# imu.net
KiCad netlist of a schematic drawn in Altium Designer
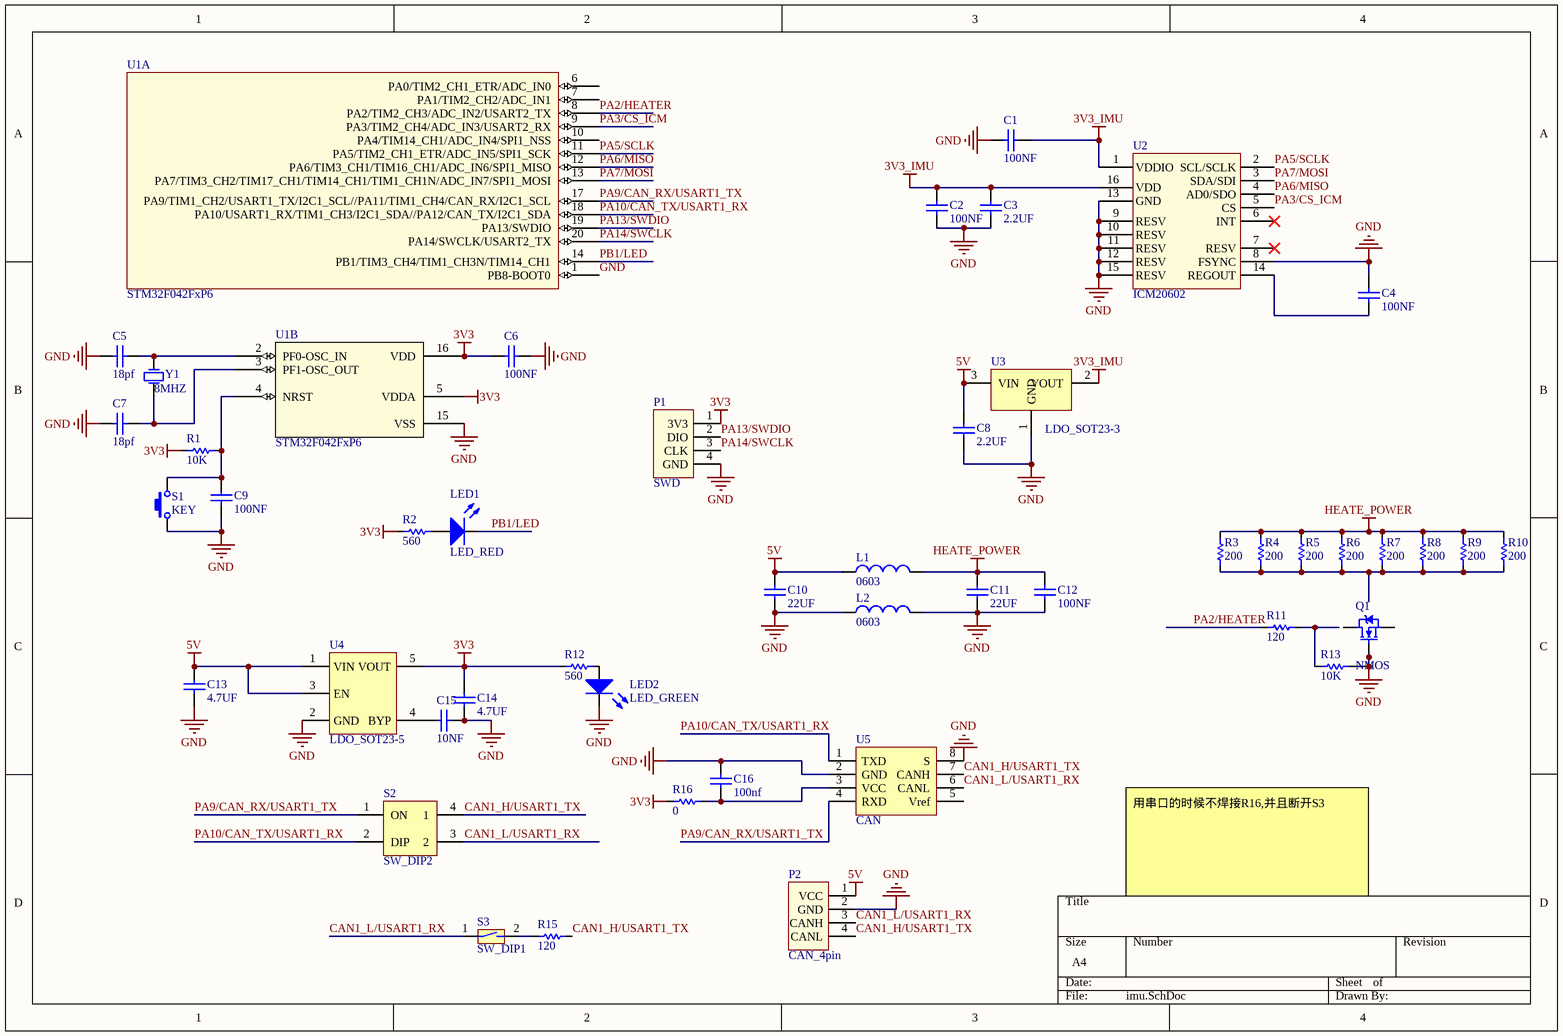
[diagram p0: imu.SchDoc]

(export (version "E")
  (design (tool "Eeschema 10.0.6"))
  (components
    (comp (ref "C1")
      (value "100NF")
      (footprint "MyComponents_v2.5:0402")
      (description "Capacitor")
      (fields (field (name "PUBLISHER") "Altium Limited"))
      (libsource (lib "MyComponents_v2.5") (part "Cap"))
    )
    (comp (ref "C2")
      (value "100NF")
      (footprint "MyComponents_v2.5:0402")
      (description "Capacitor")
      (fields (field (name "PUBLISHER") "Altium Limited"))
      (libsource (lib "MyComponents_v2.5") (part "Cap"))
    )
    (comp (ref "C3")
      (value "2.2UF")
      (footprint "MyComponents_v2.5:0402")
      (description "Capacitor")
      (fields (field (name "PUBLISHER") "Altium Limited"))
      (libsource (lib "MyComponents_v2.5") (part "Cap"))
    )
    (comp (ref "C4")
      (value "100NF")
      (footprint "MyComponents_v2.5:0402")
      (description "Capacitor")
      (fields (field (name "PUBLISHER") "Altium Limited"))
      (libsource (lib "MyComponents_v2.5") (part "Cap"))
    )
    (comp (ref "C5")
      (value "18pf")
      (footprint "MyComponents_v2.5:0402C")
      (description "Capacitor")
      (fields (field (name "PUBLISHER") "Altium Limited"))
      (libsource (lib "MyComponents_v2.5") (part "Cap"))
    )
    (comp (ref "C6")
      (value "100NF")
      (footprint "MyComponents_v2.5:0603C")
      (description "Capacitor")
      (fields (field (name "PUBLISHER") "Altium Limited"))
      (libsource (lib "MyComponents_v2.5") (part "Cap"))
    )
    (comp (ref "C7")
      (value "18pf")
      (footprint "MyComponents_v2.5:0402C")
      (description "Capacitor")
      (fields (field (name "PUBLISHER") "Altium Limited"))
      (libsource (lib "MyComponents_v2.5") (part "Cap"))
    )
    (comp (ref "C8")
      (value "2.2UF")
      (footprint "MyComponents_v2.5:0603C")
      (description "Capacitor")
      (fields (field (name "PUBLISHER") "Altium Limited"))
      (libsource (lib "MyComponents_v2.5") (part "Cap"))
    )
    (comp (ref "C9")
      (value "100NF")
      (footprint "MyComponents_v2.5:0603C")
      (description "Capacitor")
      (fields (field (name "PUBLISHER") "Altium Limited"))
      (libsource (lib "MyComponents_v2.5") (part "Cap"))
    )
    (comp (ref "C10")
      (value "22UF")
      (footprint "MyComponents_v2.5:0805c")
      (description "Capacitor")
      (fields (field (name "PUBLISHER") "Altium Limited"))
      (libsource (lib "MyComponents_v2.5") (part "Cap"))
    )
    (comp (ref "C11")
      (value "22UF")
      (footprint "MyComponents_v2.5:0805c")
      (description "Capacitor")
      (fields (field (name "PUBLISHER") "Altium Limited"))
      (libsource (lib "MyComponents_v2.5") (part "Cap"))
    )
    (comp (ref "C12")
      (value "100NF")
      (footprint "MyComponents_v2.5:0603C")
      (description "Capacitor")
      (fields (field (name "PUBLISHER") "Altium Limited"))
      (libsource (lib "MyComponents_v2.5") (part "Cap"))
    )
    (comp (ref "C13")
      (value "4.7UF")
      (footprint "MyComponents_v2.5:0603C")
      (description "Capacitor")
      (fields (field (name "PUBLISHER") "Altium Limited"))
      (libsource (lib "MyComponents_v2.5") (part "Cap"))
    )
    (comp (ref "C14")
      (value "4.7UF")
      (footprint "MyComponents_v2.5:0603C")
      (description "Capacitor")
      (fields (field (name "PUBLISHER") "Altium Limited"))
      (libsource (lib "MyComponents_v2.5") (part "Cap"))
    )
    (comp (ref "C15")
      (value "10NF")
      (footprint "MyComponents_v2.5:0603C")
      (description "Capacitor")
      (fields (field (name "PUBLISHER") "Altium Limited"))
      (libsource (lib "MyComponents_v2.5") (part "Cap"))
    )
    (comp (ref "C16")
      (value "100nf")
      (footprint "MyComponents_v2.5:0603C")
      (description "Capacitor")
      (fields (field (name "PUBLISHER") "Altium Limited"))
      (libsource (lib "MyComponents_v2.5") (part "Cap"))
    )
    (comp (ref "L1")
      (value "0603")
      (footprint "MyComponents_v2.5:0603")
      (description "Inductor")
      (fields (field (name "PUBLISHER") "Altium Limited"))
      (libsource (lib "MyComponents_v2.5") (part "Inductor"))
    )
    (comp (ref "L2")
      (value "0603")
      (footprint "MyComponents_v2.5:0603")
      (description "Inductor")
      (fields (field (name "PUBLISHER") "Altium Limited"))
      (libsource (lib "MyComponents_v2.5") (part "Inductor"))
    )
    (comp (ref "LED1")
      (value "LED_RED")
      (footprint "MyComponents_v2.5:0603LED_R")
      (description "Typical RED, GREEN, YELLOW, AMBER GaAs LED")
      (fields (field (name "PUBLISHER") "Altium Limited"))
      (libsource (lib "MyComponents_v2.5") (part "LED"))
    )
    (comp (ref "LED2")
      (value "LED_GREEN")
      (footprint "MyComponents_v2.5:0603LED_R")
      (description "Typical RED, GREEN, YELLOW, AMBER GaAs LED")
      (fields (field (name "PUBLISHER") "Altium Limited"))
      (libsource (lib "MyComponents_v2.5") (part "LED"))
    )
    (comp (ref "P1")
      (value "SWD")
      (footprint "MyComponents_v2.5:A1.25WF-4P")
      (libsource (lib "MyComponents_v2.5") (part "SWD_HEADER"))
    )
    (comp (ref "P2")
      (value "CAN_4pin")
      (footprint "MyComponents_v2.5:HY2.00MM 4X1 SMT")
      (description "CAN 4pin，带5V电源，HY2.0-4A")
      (libsource (lib "MyComponents_v2.5") (part "CAN_4pin"))
    )
    (comp (ref "Q1")
      (value "NMOS")
      (footprint "MyComponents_v2.5:SOT-23-3")
      (description "N-Channel Power MOSFET")
      (fields (field (name "PUBLISHER") "Altium Limited"))
      (libsource (lib "MyComponents_v2.5") (part "NMOS(SOT23)"))
    )
    (comp (ref "R1")
      (value "10K")
      (footprint "MyComponents_v2.5:0603R")
      (description "Resistor")
      (fields (field (name "PUBLISHER") "Altium Limited"))
      (libsource (lib "MyComponents_v2.5") (part "Res1"))
    )
    (comp (ref "R2")
      (value "560")
      (footprint "MyComponents_v2.5:0603R")
      (description "Resistor")
      (fields (field (name "PUBLISHER") "Altium Limited"))
      (libsource (lib "MyComponents_v2.5") (part "Res1"))
    )
    (comp (ref "R3")
      (value "200")
      (footprint "MyComponents_v2.5:0603R")
      (description "Resistor")
      (fields (field (name "PUBLISHER") "Altium Limited"))
      (libsource (lib "MyComponents_v2.5") (part "Res1"))
    )
    (comp (ref "R4")
      (value "200")
      (footprint "MyComponents_v2.5:0603R")
      (description "Resistor")
      (fields (field (name "PUBLISHER") "Altium Limited"))
      (libsource (lib "MyComponents_v2.5") (part "Res1"))
    )
    (comp (ref "R5")
      (value "200")
      (footprint "MyComponents_v2.5:0603R")
      (description "Resistor")
      (fields (field (name "PUBLISHER") "Altium Limited"))
      (libsource (lib "MyComponents_v2.5") (part "Res1"))
    )
    (comp (ref "R6")
      (value "200")
      (footprint "MyComponents_v2.5:0603R")
      (description "Resistor")
      (fields (field (name "PUBLISHER") "Altium Limited"))
      (libsource (lib "MyComponents_v2.5") (part "Res1"))
    )
    (comp (ref "R7")
      (value "200")
      (footprint "MyComponents_v2.5:0603R")
      (description "Resistor")
      (fields (field (name "PUBLISHER") "Altium Limited"))
      (libsource (lib "MyComponents_v2.5") (part "Res1"))
    )
    (comp (ref "R8")
      (value "200")
      (footprint "MyComponents_v2.5:0603R")
      (description "Resistor")
      (fields (field (name "PUBLISHER") "Altium Limited"))
      (libsource (lib "MyComponents_v2.5") (part "Res1"))
    )
    (comp (ref "R9")
      (value "200")
      (footprint "MyComponents_v2.5:0603R")
      (description "Resistor")
      (fields (field (name "PUBLISHER") "Altium Limited"))
      (libsource (lib "MyComponents_v2.5") (part "Res1"))
    )
    (comp (ref "R10")
      (value "200")
      (footprint "MyComponents_v2.5:0603R")
      (description "Resistor")
      (fields (field (name "PUBLISHER") "Altium Limited"))
      (libsource (lib "MyComponents_v2.5") (part "Res1"))
    )
    (comp (ref "R11")
      (value "120")
      (footprint "MyComponents_v2.5:0603R")
      (description "Resistor")
      (fields (field (name "PUBLISHER") "Altium Limited"))
      (libsource (lib "MyComponents_v2.5") (part "Res1"))
    )
    (comp (ref "R12")
      (value "560")
      (footprint "MyComponents_v2.5:0603R")
      (description "Resistor")
      (fields (field (name "PUBLISHER") "Altium Limited"))
      (libsource (lib "MyComponents_v2.5") (part "Res1"))
    )
    (comp (ref "R13")
      (value "10K")
      (footprint "MyComponents_v2.5:0603R")
      (description "Resistor")
      (fields (field (name "PUBLISHER") "Altium Limited"))
      (libsource (lib "MyComponents_v2.5") (part "Res1"))
    )
    (comp (ref "R15")
      (value "120")
      (footprint "MyComponents_v2.5:0603R")
      (description "Resistor")
      (fields (field (name "PUBLISHER") "Altium Limited"))
      (libsource (lib "MyComponents_v2.5") (part "Res1"))
    )
    (comp (ref "R16")
      (value "0")
      (footprint "MyComponents_v2.5:0603R")
      (description "Resistor")
      (fields (field (name "PUBLISHER") "Altium Limited"))
      (libsource (lib "MyComponents_v2.5") (part "Res1"))
    )
    (comp (ref "S1")
      (value "KEY")
      (footprint "MyComponents_v2.5:SW 3mmx4mm")
      (description "Button")
      (fields (field (name "PUBLISHER") "Altium Limited"))
      (libsource (lib "MyComponents_v2.5") (part "PushButton_2p"))
    )
    (comp (ref "S2")
      (value "SW_DIP2")
      (footprint "MyComponents_v2.5:SW_DIP_2x2")
      (libsource (lib "MyComponents_v2.5") (part "SW_DIP 2"))
    )
    (comp (ref "S3")
      (value "SW_DIP1")
      (footprint "MyComponents_v2.5:MSK-12C01-07")
      (libsource (lib "MyComponents_v2.5") (part "SW_DIP 1"))
    )
    (comp (ref "U1")
      (value "STM32F042FxP6")
      (footprint "MyComponents_v2.5:TSSOP20")
      (description "Imported")
      (fields (field (name "MANUFACTURER_PART_NUMBER") "stm32f042gxu"))
      (libsource (lib "MyComponents_v2.5") (part "STM32F042FxP6"))
    )
    (comp (ref "U2")
      (value "ICM20602")
      (footprint "MyComponents_v2.5:LGA-16")
      (libsource (lib "MyComponents_v2.5") (part "ICM20602"))
    )
    (comp (ref "U3")
      (value "LDO_SOT23-3")
      (footprint "MyComponents_v2.5:SOT-23-3")
      (libsource (lib "MyComponents_v2.5") (part "LDO_SOT23-3"))
    )
    (comp (ref "U4")
      (value "LDO_SOT23-5")
      (footprint "MyComponents_v2.5:SOT-23-5 L")
      (libsource (lib "MyComponents_v2.5") (part "LDO_SOT23-5"))
    )
    (comp (ref "U5")
      (value "CAN")
      (footprint "MyComponents_v2.5:SOT-23-8")
      (libsource (lib "MyComponents_v2.5") (part "CAN"))
    )
    (comp (ref "Y1")
      (value "8MHZ")
      (footprint "MyComponents_v2.5:NX3225GD")
      (description "Crystal Oscillator")
      (fields (field (name "PUBLISHER") "Altium Limited"))
      (libsource (lib "MyComponents_v2.5") (part "XTAL"))
    )
  )
  (nets
    (net (code "1") (name "/CAN1_H{slash}USART1_TX") (class "Default")
      (node (ref "P2") (pin "4") (pinfunction "CANL_4") (pintype "passive"))
      (node (ref "R15") (pin "2") (pinfunction "2_2") (pintype "passive"))
      (node (ref "S2") (pin "4") (pinfunction "1_4") (pintype "passive"))
      (node (ref "U5") (pin "7") (pinfunction "CANH_7") (pintype "passive"))
    )
    (net (code "2") (name "/CAN1_L{slash}USART1_RX") (class "Default")
      (node (ref "P2") (pin "3") (pinfunction "CANH_3") (pintype "passive"))
      (node (ref "S2") (pin "3") (pinfunction "2_3") (pintype "passive"))
      (node (ref "S3") (pin "1") (pinfunction "ON_1") (pintype "passive"))
      (node (ref "U5") (pin "6") (pinfunction "CANL_6") (pintype "passive"))
    )
    (net (code "3") (name "/PA2{slash}HEATER") (class "Default")
      (node (ref "R11") (pin "2") (pinfunction "2_2") (pintype "passive"))
      (node (ref "U1") (pin "8") (pinfunction "PA2/TIM2_CH3/ADC_IN2/USART2_TX_8") (pintype "bidirectional"))
    )
    (net (code "4") (name "/PA3{slash}CS_ICM") (class "Default")
      (node (ref "U1") (pin "9") (pinfunction "PA3/TIM2_CH4/ADC_IN3/USART2_RX_9") (pintype "bidirectional"))
      (node (ref "U2") (pin "5") (pinfunction "CS_5") (pintype "passive"))
    )
    (net (code "5") (name "/PA5{slash}SCLK") (class "Default")
      (node (ref "U1") (pin "11") (pinfunction "PA5/TIM2_CH1_ETR/ADC_IN5/SPI1_SCK_11") (pintype "bidirectional"))
      (node (ref "U2") (pin "2") (pinfunction "SCL/SCLK_2") (pintype "passive"))
    )
    (net (code "6") (name "/PA6{slash}MISO") (class "Default")
      (node (ref "U1") (pin "12") (pinfunction "PA6/TIM3_CH1/TIM16_CH1/ADC_IN6/SPI1_MISO_12") (pintype "bidirectional"))
      (node (ref "U2") (pin "4") (pinfunction "AD0/SDO_4") (pintype "passive"))
    )
    (net (code "7") (name "/PA7{slash}MOSI") (class "Default")
      (node (ref "U1") (pin "13") (pinfunction "PA7/TIM3_CH2/TIM17_CH1/TIM14_CH1/TIM1_CH1N/ADC_IN7/SPI1_MOSI_13") (pintype "bidirectional"))
      (node (ref "U2") (pin "3") (pinfunction "SDA/SDI_3") (pintype "passive"))
    )
    (net (code "8") (name "/PA9{slash}CAN_RX{slash}USART1_TX") (class "Default")
      (node (ref "S2") (pin "1") (pinfunction "ON_1") (pintype "passive"))
      (node (ref "U1") (pin "17") (pinfunction "PA9/TIM1_CH2/USART1_TX/I2C1_SCL//PA11/TIM1_CH4/CAN_RX/I2C1_SCL_17") (pintype "bidirectional"))
      (node (ref "U5") (pin "4") (pinfunction "RXD_4") (pintype "passive"))
    )
    (net (code "9") (name "/PA10{slash}CAN_TX{slash}USART1_RX") (class "Default")
      (node (ref "S2") (pin "2") (pinfunction "DIP_2") (pintype "passive"))
      (node (ref "U1") (pin "18") (pinfunction "PA10/USART1_RX/TIM1_CH3/I2C1_SDA//PA12/CAN_TX/I2C1_SDA_18") (pintype "bidirectional"))
      (node (ref "U5") (pin "1") (pinfunction "TXD_1") (pintype "passive"))
    )
    (net (code "10") (name "/PA13{slash}SWDIO") (class "Default")
      (node (ref "P1") (pin "2") (pinfunction "DIO_2") (pintype "passive"))
      (node (ref "U1") (pin "19") (pinfunction "PA13/SWDIO_19") (pintype "bidirectional"))
    )
    (net (code "11") (name "/PA14{slash}SWCLK") (class "Default")
      (node (ref "P1") (pin "3") (pinfunction "CLK_3") (pintype "passive"))
      (node (ref "U1") (pin "20") (pinfunction "PA14/SWCLK/USART2_TX_20") (pintype "bidirectional"))
    )
    (net (code "12") (name "/PB1{slash}LED") (class "Default")
      (node (ref "LED1") (pin "2") (pinfunction "2_2") (pintype "passive"))
      (node (ref "U1") (pin "14") (pinfunction "PB1/TIM3_CH4/TIM1_CH3N/TIM14_CH1_14") (pintype "bidirectional"))
    )
    (net (code "13") (name "3V3") (class "Default")
      (node (ref "C14") (pin "1") (pinfunction "1_1") (pintype "passive"))
      (node (ref "C6") (pin "2") (pinfunction "2_2") (pintype "passive"))
      (node (ref "P1") (pin "1") (pinfunction "3V3_1") (pintype "passive"))
      (node (ref "R1") (pin "1") (pinfunction "1_1") (pintype "passive"))
      (node (ref "R12") (pin "1") (pinfunction "1_1") (pintype "passive"))
      (node (ref "R16") (pin "1") (pinfunction "1_1") (pintype "passive"))
      (node (ref "R2") (pin "1") (pinfunction "1_1") (pintype "passive"))
      (node (ref "U1") (pin "16") (pinfunction "VDD_16") (pintype "power_in"))
      (node (ref "U1") (pin "5") (pinfunction "VDDA_5") (pintype "power_in"))
      (node (ref "U4") (pin "5") (pinfunction "VOUT_5") (pintype "passive"))
    )
    (net (code "14") (name "3V3_IMU") (class "Default")
      (node (ref "C1") (pin "1") (pinfunction "1_1") (pintype "passive"))
      (node (ref "C2") (pin "2") (pinfunction "2_2") (pintype "passive"))
      (node (ref "C3") (pin "1") (pinfunction "1_1") (pintype "passive"))
      (node (ref "U2") (pin "1") (pinfunction "VDDIO_1") (pintype "passive"))
      (node (ref "U2") (pin "16") (pinfunction "VDD_16") (pintype "passive"))
      (node (ref "U3") (pin "2") (pinfunction "VOUT_2") (pintype "passive"))
    )
    (net (code "15") (name "5V") (class "Default")
      (node (ref "C10") (pin "1") (pinfunction "1_1") (pintype "passive"))
      (node (ref "C13") (pin "2") (pinfunction "2_2") (pintype "passive"))
      (node (ref "C8") (pin "1") (pinfunction "1_1") (pintype "passive"))
      (node (ref "L1") (pin "1") (pinfunction "1_1") (pintype "passive"))
      (node (ref "P2") (pin "1") (pinfunction "VCC_1") (pintype "passive"))
      (node (ref "U3") (pin "3") (pinfunction "VIN_3") (pintype "passive"))
      (node (ref "U4") (pin "1") (pinfunction "VIN_1") (pintype "passive"))
      (node (ref "U4") (pin "3") (pinfunction "EN_3") (pintype "passive"))
    )
    (net (code "16") (name "GND") (class "Default")
      (node (ref "C1") (pin "2") (pinfunction "2_2") (pintype "passive"))
      (node (ref "C10") (pin "2") (pinfunction "2_2") (pintype "passive"))
      (node (ref "C11") (pin "2") (pinfunction "2_2") (pintype "passive"))
      (node (ref "C12") (pin "2") (pinfunction "2_2") (pintype "passive"))
      (node (ref "C13") (pin "1") (pinfunction "1_1") (pintype "passive"))
      (node (ref "C14") (pin "2") (pinfunction "2_2") (pintype "passive"))
      (node (ref "C15") (pin "1") (pinfunction "1_1") (pintype "passive"))
      (node (ref "C16") (pin "1") (pinfunction "1_1") (pintype "passive"))
      (node (ref "C2") (pin "1") (pinfunction "1_1") (pintype "passive"))
      (node (ref "C3") (pin "2") (pinfunction "2_2") (pintype "passive"))
      (node (ref "C4") (pin "1") (pinfunction "1_1") (pintype "passive"))
      (node (ref "C5") (pin "1") (pinfunction "1_1") (pintype "passive"))
      (node (ref "C6") (pin "1") (pinfunction "1_1") (pintype "passive"))
      (node (ref "C7") (pin "1") (pinfunction "1_1") (pintype "passive"))
      (node (ref "C8") (pin "2") (pinfunction "2_2") (pintype "passive"))
      (node (ref "C9") (pin "1") (pinfunction "1_1") (pintype "passive"))
      (node (ref "L2") (pin "1") (pinfunction "1_1") (pintype "passive"))
      (node (ref "L2") (pin "2") (pinfunction "2_2") (pintype "passive"))
      (node (ref "LED2") (pin "2") (pinfunction "2_2") (pintype "passive"))
      (node (ref "P1") (pin "4") (pinfunction "GND_4") (pintype "passive"))
      (node (ref "P2") (pin "2") (pinfunction "GND_2") (pintype "passive"))
      (node (ref "Q1") (pin "1") (pinfunction "G_1") (pintype "passive"))
      (node (ref "R13") (pin "1") (pinfunction "1_1") (pintype "passive"))
      (node (ref "S1") (pin "1") (pinfunction "1_1") (pintype "passive"))
      (node (ref "U1") (pin "1") (pinfunction "PB8-BOOT0_1") (pintype "bidirectional"))
      (node (ref "U1") (pin "15") (pinfunction "VSS_15") (pintype "power_in"))
      (node (ref "U2") (pin "10") (pinfunction "RESV_10") (pintype "passive"))
      (node (ref "U2") (pin "11") (pinfunction "RESV_11") (pintype "passive"))
      (node (ref "U2") (pin "12") (pinfunction "RESV_12") (pintype "passive"))
      (node (ref "U2") (pin "13") (pinfunction "GND_13") (pintype "passive"))
      (node (ref "U2") (pin "15") (pinfunction "RESV_15") (pintype "passive"))
      (node (ref "U2") (pin "8") (pinfunction "FSYNC_8") (pintype "passive"))
      (node (ref "U2") (pin "9") (pinfunction "RESV_9") (pintype "passive"))
      (node (ref "U3") (pin "1") (pinfunction "GND_1") (pintype "passive"))
      (node (ref "U4") (pin "2") (pinfunction "GND_2") (pintype "passive"))
      (node (ref "U5") (pin "2") (pinfunction "GND_2") (pintype "passive"))
      (node (ref "U5") (pin "8") (pinfunction "S_8") (pintype "passive"))
    )
    (net (code "17") (name "HEATE_POWER") (class "Default")
      (node (ref "C11") (pin "1") (pinfunction "1_1") (pintype "passive"))
      (node (ref "C12") (pin "1") (pinfunction "1_1") (pintype "passive"))
      (node (ref "L1") (pin "2") (pinfunction "2_2") (pintype "passive"))
      (node (ref "R10") (pin "2") (pinfunction "2_2") (pintype "passive"))
      (node (ref "R3") (pin "2") (pinfunction "2_2") (pintype "passive"))
      (node (ref "R4") (pin "2") (pinfunction "2_2") (pintype "passive"))
      (node (ref "R5") (pin "2") (pinfunction "2_2") (pintype "passive"))
      (node (ref "R6") (pin "2") (pinfunction "2_2") (pintype "passive"))
      (node (ref "R7") (pin "2") (pinfunction "2_2") (pintype "passive"))
      (node (ref "R8") (pin "2") (pinfunction "2_2") (pintype "passive"))
      (node (ref "R9") (pin "2") (pinfunction "2_2") (pintype "passive"))
    )
    (net (code "18") (name "Net-(LED1-Pad1)") (class "Default")
      (node (ref "LED1") (pin "1") (pinfunction "1_1") (pintype "passive"))
      (node (ref "R2") (pin "2") (pinfunction "2_2") (pintype "passive"))
    )
    (net (code "19") (name "Net-(LED2-Pad1)") (class "Default")
      (node (ref "LED2") (pin "1") (pinfunction "1_1") (pintype "passive"))
      (node (ref "R12") (pin "2") (pinfunction "2_2") (pintype "passive"))
    )
    (net (code "20") (name "Net-(R10-Pad1)") (class "Default")
      (node (ref "R10") (pin "1") (pinfunction "1_1") (pintype "passive"))
      (node (ref "R3") (pin "1") (pinfunction "1_1") (pintype "passive"))
      (node (ref "R4") (pin "1") (pinfunction "1_1") (pintype "passive"))
      (node (ref "R5") (pin "1") (pinfunction "1_1") (pintype "passive"))
      (node (ref "R6") (pin "1") (pinfunction "1_1") (pintype "passive"))
      (node (ref "R7") (pin "1") (pinfunction "1_1") (pintype "passive"))
      (node (ref "R8") (pin "1") (pinfunction "1_1") (pintype "passive"))
      (node (ref "R9") (pin "1") (pinfunction "1_1") (pintype "passive"))
    )
    (net (code "21") (name "Net-(R11-Pad1)") (class "Default")
      (node (ref "R11") (pin "1") (pinfunction "1_1") (pintype "passive"))
      (node (ref "R13") (pin "2") (pinfunction "2_2") (pintype "passive"))
    )
    (net (code "22") (name "Net-(S3-DIP)") (class "Default")
      (node (ref "R15") (pin "1") (pinfunction "1_1") (pintype "passive"))
      (node (ref "S3") (pin "2") (pinfunction "DIP_2") (pintype "passive"))
    )
    (net (code "23") (name "Net-(U1B-NRST)") (class "Default")
      (node (ref "C9") (pin "2") (pinfunction "2_2") (pintype "passive"))
      (node (ref "R1") (pin "2") (pinfunction "2_2") (pintype "passive"))
      (node (ref "S1") (pin "2") (pinfunction "2_2") (pintype "passive"))
      (node (ref "U1") (pin "4") (pinfunction "NRST_4") (pintype "bidirectional"))
    )
    (net (code "24") (name "Net-(U1B-PF0-OSC_IN)") (class "Default")
      (node (ref "C5") (pin "2") (pinfunction "2_2") (pintype "passive"))
      (node (ref "U1") (pin "2") (pinfunction "PF0-OSC_IN_2") (pintype "bidirectional"))
      (node (ref "Y1") (pin "2") (pinfunction "OSC2_2") (pintype "passive"))
    )
    (net (code "25") (name "Net-(U1B-PF1-OSC_OUT)") (class "Default")
      (node (ref "C7") (pin "2") (pinfunction "2_2") (pintype "passive"))
      (node (ref "U1") (pin "3") (pinfunction "PF1-OSC_OUT_3") (pintype "bidirectional"))
      (node (ref "Y1") (pin "1") (pinfunction "OSC1_1") (pintype "passive"))
    )
    (net (code "26") (name "Net-(U2-REGOUT)") (class "Default")
      (node (ref "C4") (pin "2") (pinfunction "2_2") (pintype "passive"))
      (node (ref "U2") (pin "14") (pinfunction "REGOUT_14") (pintype "passive"))
    )
    (net (code "27") (name "Net-(U4-BYP)") (class "Default")
      (node (ref "C15") (pin "2") (pinfunction "2_2") (pintype "passive"))
      (node (ref "U4") (pin "4") (pinfunction "BYP_4") (pintype "passive"))
    )
    (net (code "28") (name "Net-(U5-VCC)") (class "Default")
      (node (ref "C16") (pin "2") (pinfunction "2_2") (pintype "passive"))
      (node (ref "R16") (pin "2") (pinfunction "2_2") (pintype "passive"))
      (node (ref "U5") (pin "3") (pinfunction "VCC_3") (pintype "passive"))
    )
    (net (code "29") (name "unconnected-(Q1-D-Pad3)") (class "Default")
      (node (ref "Q1") (pin "3") (pinfunction "D_3") (pintype "passive"))
    )
    (net (code "30") (name "unconnected-(Q1-S-Pad2)") (class "Default")
      (node (ref "Q1") (pin "2") (pinfunction "S_2") (pintype "passive"))
    )
    (net (code "31") (name "unconnected-(U1A-PA0{slash}TIM2_CH1_ETR{slash}ADC_IN0-Pad6)") (class "Default")
      (node (ref "U1") (pin "6") (pinfunction "PA0/TIM2_CH1_ETR/ADC_IN0_6") (pintype "bidirectional"))
    )
    (net (code "32") (name "unconnected-(U1A-PA1{slash}TIM2_CH2{slash}ADC_IN1-Pad7)") (class "Default")
      (node (ref "U1") (pin "7") (pinfunction "PA1/TIM2_CH2/ADC_IN1_7") (pintype "bidirectional"))
    )
    (net (code "33") (name "unconnected-(U1A-PA4{slash}TIM14_CH1{slash}ADC_IN4{slash}SPI1_NSS-Pad10)") (class "Default")
      (node (ref "U1") (pin "10") (pinfunction "PA4/TIM14_CH1/ADC_IN4/SPI1_NSS_10") (pintype "bidirectional"))
    )
    (net (code "34") (name "unconnected-(U2-INT-Pad6)") (class "Default")
      (node (ref "U2") (pin "6") (pinfunction "INT_6") (pintype "passive+no_connect"))
    )
    (net (code "35") (name "unconnected-(U2-RESV-Pad7)") (class "Default")
      (node (ref "U2") (pin "7") (pinfunction "RESV_7") (pintype "passive+no_connect"))
    )
    (net (code "36") (name "unconnected-(U5-Vref-Pad5)") (class "Default")
      (node (ref "U5") (pin "5") (pinfunction "Vref_5") (pintype "passive"))
    )
  )
)
